# merkur-connect-pi-expansionboard.net
KiCad netlist of a schematic drawn in EAGLE
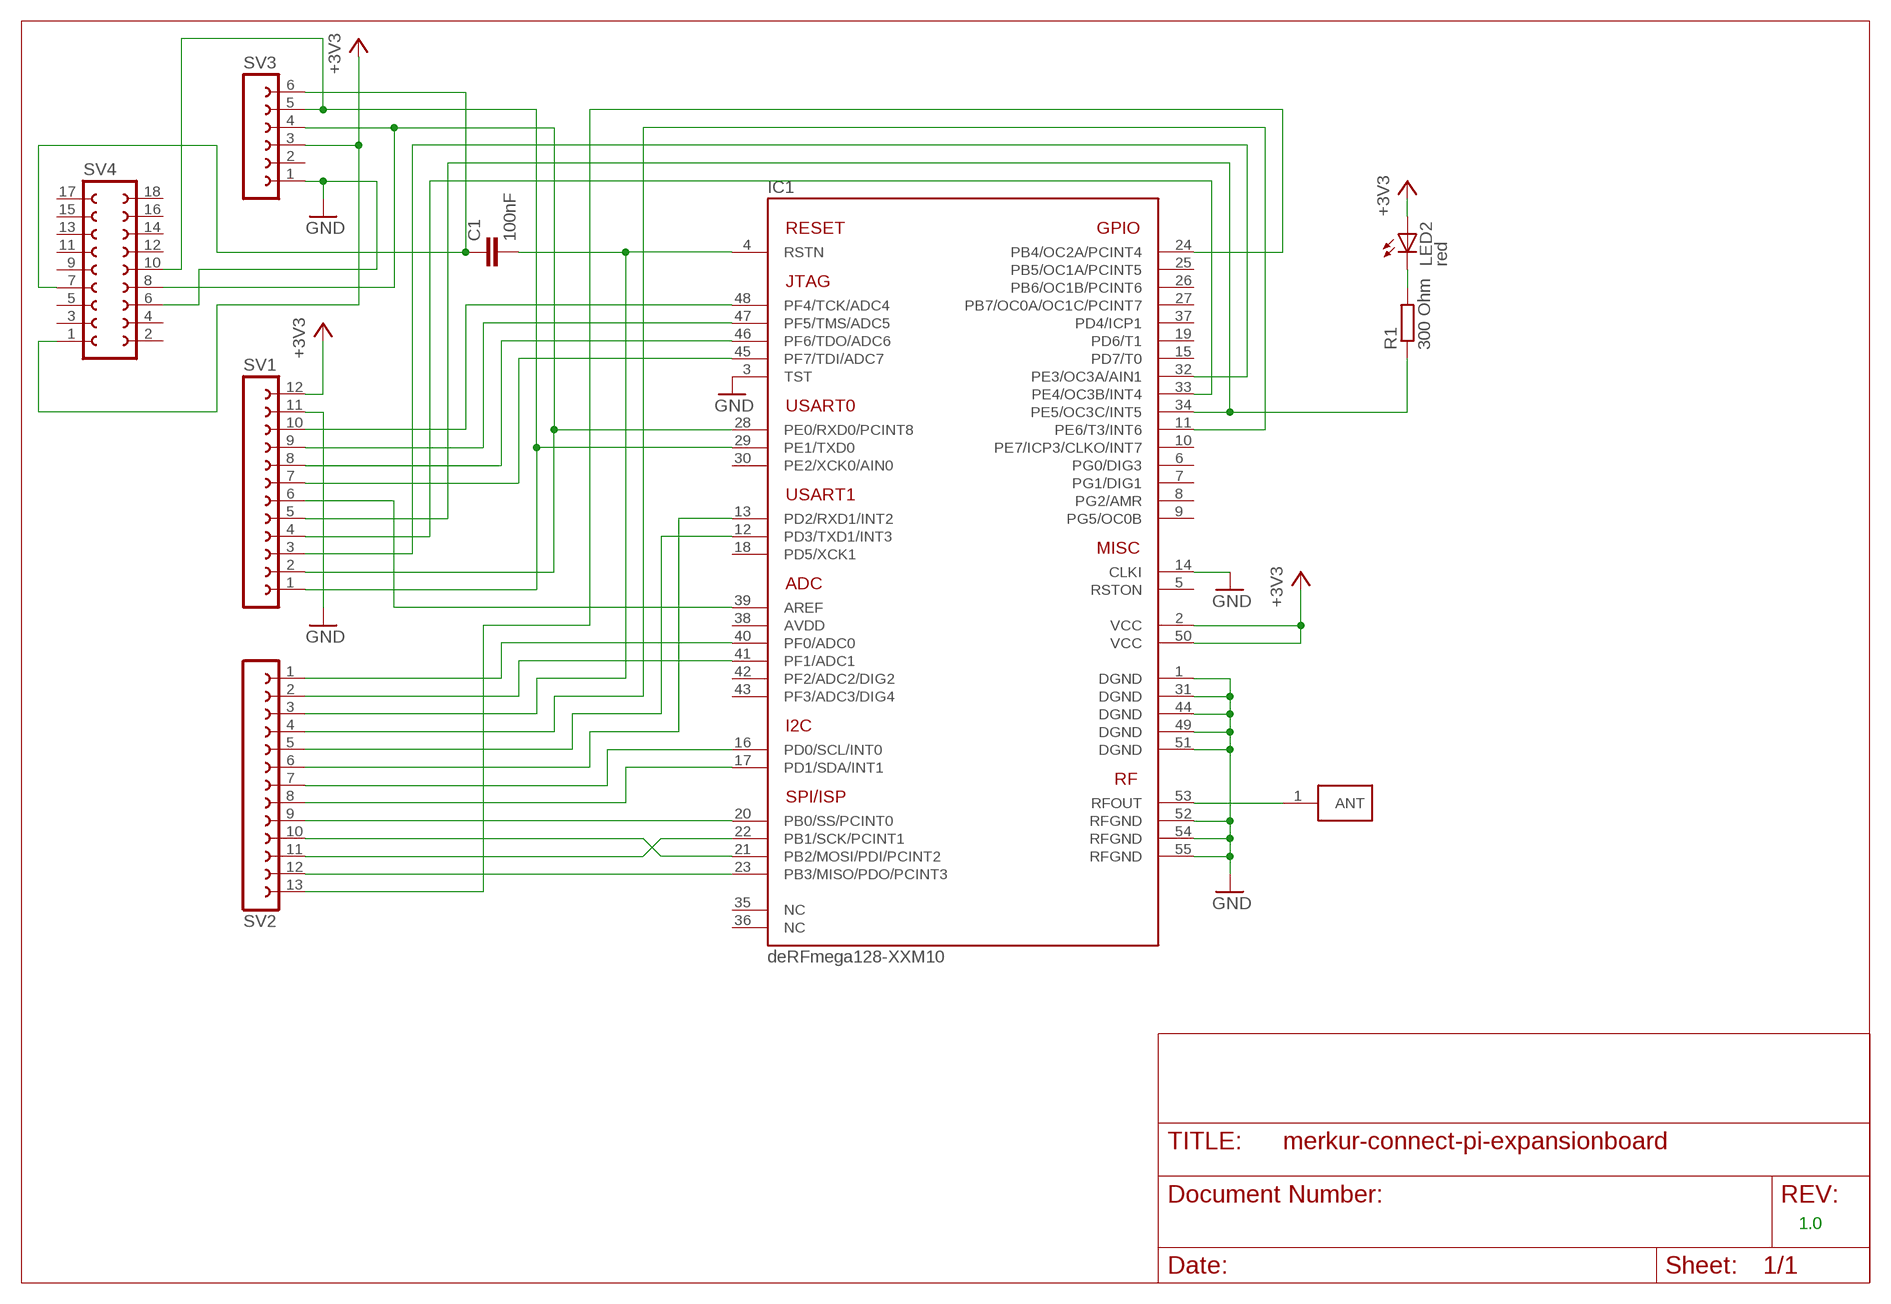
[diagram p0: schematic, sheet 1]

(export (version "E")
  (design (tool "Eeschema 10.0.6"))
  (components
    (comp (ref "C1")
      (value "100nF")
      (footprint "eagle-import:C0603")
      (libsource (lib "eagle-import") (part "C-EUC0603"))
    )
    (comp (ref "IC1")
      (value "DERFMEGA128-XXM10")
      (footprint "eagle-import:A-M10")
      (libsource (lib "eagle-import") (part "DERFMEGA128-XXM10"))
    )
    (comp (ref "LED2")
      (value "red")
      (footprint "eagle-import:CHIP-LED0603")
      (libsource (lib "eagle-import") (part "LEDCHIP-LED0603"))
    )
    (comp (ref "R1")
      (value "300 Ohm")
      (footprint "eagle-import:R0603")
      (libsource (lib "eagle-import") (part "R-EU_R0603"))
    )
    (comp (ref "SV1")
      (value "FE12-1")
      (footprint "eagle-import:FE12")
      (libsource (lib "eagle-import") (part "FE12-1"))
    )
    (comp (ref "SV2")
      (value "FE13-1")
      (footprint "eagle-import:FE13")
      (libsource (lib "eagle-import") (part "FE13-1"))
    )
    (comp (ref "SV3")
      (value "FE06-1")
      (footprint "eagle-import:FE06")
      (libsource (lib "eagle-import") (part "FE06-1"))
    )
    (comp (ref "SV4")
      (value "FE09-2")
      (footprint "eagle-import:FE09-2")
      (libsource (lib "eagle-import") (part "FE09-2"))
    )
    (comp (ref "U$1")
      (value "PAD")
      (footprint "eagle-import:FE05-1")
      (libsource (lib "eagle-import") (part "PAD"))
    )
  )
  (nets
    (net (code "1") (name "+3V3") (class "Default")
      (node (ref "IC1") (pin "2") (pinfunction "VCC_2") (pintype "power_in"))
      (node (ref "IC1") (pin "50") (pinfunction "VCC_50") (pintype "power_in"))
      (node (ref "LED2") (pin "A") (pinfunction "A_A") (pintype "passive"))
      (node (ref "SV1") (pin "12") (pinfunction "12_12") (pintype "passive"))
      (node (ref "SV3") (pin "3") (pinfunction "3_3") (pintype "passive"))
      (node (ref "SV4") (pin "1") (pinfunction "1_1") (pintype "passive"))
    )
    (net (code "2") (name "/AVDD") (class "Default")
      (node (ref "IC1") (pin "38") (pinfunction "AVDD_38") (pintype "power_in"))
    )
    (net (code "3") (name "GND") (class "Default")
      (node (ref "IC1") (pin "1") (pinfunction "DGND_1") (pintype "power_in"))
      (node (ref "IC1") (pin "14") (pinfunction "CLKI_14") (pintype "input"))
      (node (ref "IC1") (pin "3") (pinfunction "TST_3") (pintype "bidirectional"))
      (node (ref "IC1") (pin "31") (pinfunction "DGND_31") (pintype "power_in"))
      (node (ref "IC1") (pin "44") (pinfunction "DGND_44") (pintype "power_in"))
      (node (ref "IC1") (pin "49") (pinfunction "DGND_49") (pintype "power_in"))
      (node (ref "IC1") (pin "51") (pinfunction "DGND_51") (pintype "power_in"))
      (node (ref "IC1") (pin "52") (pinfunction "RFGND_52") (pintype "power_in"))
      (node (ref "IC1") (pin "54") (pinfunction "RFGND_54") (pintype "power_in"))
      (node (ref "IC1") (pin "55") (pinfunction "RFGND_55") (pintype "power_in"))
      (node (ref "SV1") (pin "11") (pinfunction "11_11") (pintype "passive"))
      (node (ref "SV3") (pin "1") (pinfunction "1_1") (pintype "passive"))
      (node (ref "SV4") (pin "6") (pinfunction "6_6") (pintype "passive"))
    )
    (net (code "4") (name "Net-(C1-Pad1)") (class "Default")
      (node (ref "C1") (pin "1") (pinfunction "1_1") (pintype "passive"))
      (node (ref "SV3") (pin "6") (pinfunction "6_6") (pintype "passive"))
      (node (ref "SV4") (pin "7") (pinfunction "7_7") (pintype "passive"))
    )
    (net (code "5") (name "Net-(IC1-AREF)") (class "Default")
      (node (ref "IC1") (pin "39") (pinfunction "AREF_39") (pintype "bidirectional"))
      (node (ref "SV1") (pin "6") (pinfunction "6_6") (pintype "passive"))
    )
    (net (code "6") (name "Net-(IC1-PB0{slash}SS{slash}PCINT0)") (class "Default")
      (node (ref "IC1") (pin "20") (pinfunction "PB0/SS/PCINT0_20") (pintype "bidirectional"))
      (node (ref "SV2") (pin "9") (pinfunction "9_9") (pintype "passive"))
    )
    (net (code "7") (name "Net-(IC1-PB1{slash}SCK{slash}PCINT1)") (class "Default")
      (node (ref "IC1") (pin "22") (pinfunction "PB1/SCK/PCINT1_22") (pintype "bidirectional"))
      (node (ref "SV2") (pin "11") (pinfunction "11_11") (pintype "passive"))
    )
    (net (code "8") (name "Net-(IC1-PB2{slash}MOSI{slash}PDI{slash}PCINT2)") (class "Default")
      (node (ref "IC1") (pin "21") (pinfunction "PB2/MOSI/PDI/PCINT2_21") (pintype "bidirectional"))
      (node (ref "SV2") (pin "10") (pinfunction "10_10") (pintype "passive"))
    )
    (net (code "9") (name "Net-(IC1-PB3{slash}MISO{slash}PDO{slash}PCINT3)") (class "Default")
      (node (ref "IC1") (pin "23") (pinfunction "PB3/MISO/PDO/PCINT3_23") (pintype "bidirectional"))
      (node (ref "SV2") (pin "12") (pinfunction "12_12") (pintype "passive"))
    )
    (net (code "10") (name "Net-(IC1-PB4{slash}OC2A{slash}PCINT4)") (class "Default")
      (node (ref "IC1") (pin "24") (pinfunction "PB4/OC2A/PCINT4_24") (pintype "bidirectional"))
      (node (ref "SV2") (pin "13") (pinfunction "13_13") (pintype "passive"))
    )
    (net (code "11") (name "Net-(IC1-PD0{slash}SCL{slash}INT0)") (class "Default")
      (node (ref "IC1") (pin "16") (pinfunction "PD0/SCL/INT0_16") (pintype "bidirectional"))
      (node (ref "SV2") (pin "7") (pinfunction "7_7") (pintype "passive"))
    )
    (net (code "12") (name "Net-(IC1-PD1{slash}SDA{slash}INT1)") (class "Default")
      (node (ref "IC1") (pin "17") (pinfunction "PD1/SDA/INT1_17") (pintype "bidirectional"))
      (node (ref "SV2") (pin "8") (pinfunction "8_8") (pintype "passive"))
    )
    (net (code "13") (name "Net-(IC1-PD2{slash}RXD1{slash}INT2)") (class "Default")
      (node (ref "IC1") (pin "13") (pinfunction "PD2/RXD1/INT2_13") (pintype "bidirectional"))
      (node (ref "SV2") (pin "6") (pinfunction "6_6") (pintype "passive"))
    )
    (net (code "14") (name "Net-(IC1-PD3{slash}TXD1{slash}INT3)") (class "Default")
      (node (ref "IC1") (pin "12") (pinfunction "PD3/TXD1/INT3_12") (pintype "bidirectional"))
      (node (ref "SV2") (pin "5") (pinfunction "5_5") (pintype "passive"))
    )
    (net (code "15") (name "Net-(IC1-PE0{slash}RXD0{slash}PCINT8)") (class "Default")
      (node (ref "IC1") (pin "28") (pinfunction "PE0/RXD0/PCINT8_28") (pintype "bidirectional"))
      (node (ref "SV1") (pin "2") (pinfunction "2_2") (pintype "passive"))
      (node (ref "SV3") (pin "4") (pinfunction "4_4") (pintype "passive"))
      (node (ref "SV4") (pin "8") (pinfunction "8_8") (pintype "passive"))
    )
    (net (code "16") (name "Net-(IC1-PE1{slash}TXD0)") (class "Default")
      (node (ref "IC1") (pin "29") (pinfunction "PE1/TXD0_29") (pintype "bidirectional"))
      (node (ref "SV1") (pin "1") (pinfunction "1_1") (pintype "passive"))
      (node (ref "SV3") (pin "5") (pinfunction "5_5") (pintype "passive"))
      (node (ref "SV4") (pin "10") (pinfunction "10_10") (pintype "passive"))
    )
    (net (code "17") (name "Net-(IC1-PE3{slash}OC3A{slash}AIN1)") (class "Default")
      (node (ref "IC1") (pin "32") (pinfunction "PE3/OC3A/AIN1_32") (pintype "bidirectional"))
      (node (ref "SV1") (pin "3") (pinfunction "3_3") (pintype "passive"))
    )
    (net (code "18") (name "Net-(IC1-PE4{slash}OC3B{slash}INT4)") (class "Default")
      (node (ref "IC1") (pin "33") (pinfunction "PE4/OC3B/INT4_33") (pintype "bidirectional"))
      (node (ref "SV1") (pin "4") (pinfunction "4_4") (pintype "passive"))
    )
    (net (code "19") (name "Net-(IC1-PE5{slash}OC3C{slash}INT5)") (class "Default")
      (node (ref "IC1") (pin "34") (pinfunction "PE5/OC3C/INT5_34") (pintype "bidirectional"))
      (node (ref "R1") (pin "1") (pinfunction "1_1") (pintype "passive"))
      (node (ref "SV1") (pin "5") (pinfunction "5_5") (pintype "passive"))
    )
    (net (code "20") (name "Net-(IC1-PE6{slash}T3{slash}INT6)") (class "Default")
      (node (ref "IC1") (pin "11") (pinfunction "PE6/T3/INT6_11") (pintype "bidirectional"))
      (node (ref "SV2") (pin "4") (pinfunction "4_4") (pintype "passive"))
    )
    (net (code "21") (name "Net-(IC1-PF0{slash}ADC0)") (class "Default")
      (node (ref "IC1") (pin "40") (pinfunction "PF0/ADC0_40") (pintype "bidirectional"))
      (node (ref "SV2") (pin "1") (pinfunction "1_1") (pintype "passive"))
    )
    (net (code "22") (name "Net-(IC1-PF1{slash}ADC1)") (class "Default")
      (node (ref "IC1") (pin "41") (pinfunction "PF1/ADC1_41") (pintype "bidirectional"))
      (node (ref "SV2") (pin "2") (pinfunction "2_2") (pintype "passive"))
    )
    (net (code "23") (name "Net-(IC1-PF4{slash}TCK{slash}ADC4)") (class "Default")
      (node (ref "IC1") (pin "48") (pinfunction "PF4/TCK/ADC4_48") (pintype "bidirectional"))
      (node (ref "SV1") (pin "10") (pinfunction "10_10") (pintype "passive"))
    )
    (net (code "24") (name "Net-(IC1-PF5{slash}TMS{slash}ADC5)") (class "Default")
      (node (ref "IC1") (pin "47") (pinfunction "PF5/TMS/ADC5_47") (pintype "bidirectional"))
      (node (ref "SV1") (pin "9") (pinfunction "9_9") (pintype "passive"))
    )
    (net (code "25") (name "Net-(IC1-PF6{slash}TDO{slash}ADC6)") (class "Default")
      (node (ref "IC1") (pin "46") (pinfunction "PF6/TDO/ADC6_46") (pintype "bidirectional"))
      (node (ref "SV1") (pin "8") (pinfunction "8_8") (pintype "passive"))
    )
    (net (code "26") (name "Net-(IC1-PF7{slash}TDI{slash}ADC7)") (class "Default")
      (node (ref "IC1") (pin "45") (pinfunction "PF7/TDI/ADC7_45") (pintype "bidirectional"))
      (node (ref "SV1") (pin "7") (pinfunction "7_7") (pintype "passive"))
    )
    (net (code "27") (name "Net-(IC1-RFOUT)") (class "Default")
      (node (ref "IC1") (pin "53") (pinfunction "RFOUT_53") (pintype "power_in"))
      (node (ref "U$1") (pin "1") (pinfunction "ANT_1") (pintype "output"))
    )
    (net (code "28") (name "Net-(IC1-RSTN)") (class "Default")
      (node (ref "C1") (pin "2") (pinfunction "2_2") (pintype "passive"))
      (node (ref "IC1") (pin "4") (pinfunction "RSTN_4") (pintype "input"))
      (node (ref "SV2") (pin "3") (pinfunction "3_3") (pintype "passive"))
    )
    (net (code "29") (name "Net-(LED2-PadC)") (class "Default")
      (node (ref "LED2") (pin "C") (pinfunction "C_C") (pintype "passive"))
      (node (ref "R1") (pin "2") (pinfunction "2_2") (pintype "passive"))
    )
    (net (code "30") (name "unconnected-(IC1-NC-Pad35)") (class "Default")
      (node (ref "IC1") (pin "35") (pinfunction "NC_35") (pintype "no_connect"))
    )
    (net (code "31") (name "unconnected-(IC1-NC-Pad36)") (class "Default")
      (node (ref "IC1") (pin "36") (pinfunction "NC_36") (pintype "no_connect"))
    )
    (net (code "32") (name "unconnected-(IC1-PB5{slash}OC1A{slash}PCINT5-Pad25)") (class "Default")
      (node (ref "IC1") (pin "25") (pinfunction "PB5/OC1A/PCINT5_25") (pintype "bidirectional"))
    )
    (net (code "33") (name "unconnected-(IC1-PB6{slash}OC1B{slash}PCINT6-Pad26)") (class "Default")
      (node (ref "IC1") (pin "26") (pinfunction "PB6/OC1B/PCINT6_26") (pintype "bidirectional"))
    )
    (net (code "34") (name "unconnected-(IC1-PB7{slash}OC0A{slash}OC1C{slash}PCINT7-Pad27)") (class "Default")
      (node (ref "IC1") (pin "27") (pinfunction "PB7/OC0A/OC1C/PCINT7_27") (pintype "bidirectional"))
    )
    (net (code "35") (name "unconnected-(IC1-PD4{slash}ICP1-Pad37)") (class "Default")
      (node (ref "IC1") (pin "37") (pinfunction "PD4/ICP1_37") (pintype "bidirectional"))
    )
    (net (code "36") (name "unconnected-(IC1-PD5{slash}XCK1-Pad18)") (class "Default")
      (node (ref "IC1") (pin "18") (pinfunction "PD5/XCK1_18") (pintype "bidirectional"))
    )
    (net (code "37") (name "unconnected-(IC1-PD6{slash}T1-Pad19)") (class "Default")
      (node (ref "IC1") (pin "19") (pinfunction "PD6/T1_19") (pintype "bidirectional"))
    )
    (net (code "38") (name "unconnected-(IC1-PD7{slash}T0-Pad15)") (class "Default")
      (node (ref "IC1") (pin "15") (pinfunction "PD7/T0_15") (pintype "bidirectional"))
    )
    (net (code "39") (name "unconnected-(IC1-PE2{slash}XCK0{slash}AIN0-Pad30)") (class "Default")
      (node (ref "IC1") (pin "30") (pinfunction "PE2/XCK0/AIN0_30") (pintype "bidirectional"))
    )
    (net (code "40") (name "unconnected-(IC1-PE7{slash}ICP3{slash}CLKO{slash}INT7-Pad10)") (class "Default")
      (node (ref "IC1") (pin "10") (pinfunction "PE7/ICP3/CLKO/INT7_10") (pintype "bidirectional"))
    )
    (net (code "41") (name "unconnected-(IC1-PF2{slash}ADC2{slash}DIG2-Pad42)") (class "Default")
      (node (ref "IC1") (pin "42") (pinfunction "PF2/ADC2/DIG2_42") (pintype "bidirectional"))
    )
    (net (code "42") (name "unconnected-(IC1-PF3{slash}ADC3{slash}DIG4-Pad43)") (class "Default")
      (node (ref "IC1") (pin "43") (pinfunction "PF3/ADC3/DIG4_43") (pintype "bidirectional"))
    )
    (net (code "43") (name "unconnected-(IC1-PG0{slash}DIG3-Pad6)") (class "Default")
      (node (ref "IC1") (pin "6") (pinfunction "PG0/DIG3_6") (pintype "bidirectional"))
    )
    (net (code "44") (name "unconnected-(IC1-PG1{slash}DIG1-Pad7)") (class "Default")
      (node (ref "IC1") (pin "7") (pinfunction "PG1/DIG1_7") (pintype "bidirectional"))
    )
    (net (code "45") (name "unconnected-(IC1-PG2{slash}AMR-Pad8)") (class "Default")
      (node (ref "IC1") (pin "8") (pinfunction "PG2/AMR_8") (pintype "bidirectional"))
    )
    (net (code "46") (name "unconnected-(IC1-PG5{slash}OC0B-Pad9)") (class "Default")
      (node (ref "IC1") (pin "9") (pinfunction "PG5/OC0B_9") (pintype "bidirectional"))
    )
    (net (code "47") (name "unconnected-(IC1-RSTON-Pad5)") (class "Default")
      (node (ref "IC1") (pin "5") (pinfunction "RSTON_5") (pintype "output"))
    )
    (net (code "48") (name "unconnected-(SV3-Pad2)") (class "Default")
      (node (ref "SV3") (pin "2") (pinfunction "2_2") (pintype "passive"))
    )
    (net (code "49") (name "unconnected-(SV4-Pad2)") (class "Default")
      (node (ref "SV4") (pin "2") (pinfunction "2_2") (pintype "passive"))
    )
    (net (code "50") (name "unconnected-(SV4-Pad3)") (class "Default")
      (node (ref "SV4") (pin "3") (pinfunction "3_3") (pintype "passive"))
    )
    (net (code "51") (name "unconnected-(SV4-Pad4)") (class "Default")
      (node (ref "SV4") (pin "4") (pinfunction "4_4") (pintype "passive"))
    )
    (net (code "52") (name "unconnected-(SV4-Pad5)") (class "Default")
      (node (ref "SV4") (pin "5") (pinfunction "5_5") (pintype "passive"))
    )
    (net (code "53") (name "unconnected-(SV4-Pad9)") (class "Default")
      (node (ref "SV4") (pin "9") (pinfunction "9_9") (pintype "passive"))
    )
    (net (code "54") (name "unconnected-(SV4-Pad11)") (class "Default")
      (node (ref "SV4") (pin "11") (pinfunction "11_11") (pintype "passive"))
    )
    (net (code "55") (name "unconnected-(SV4-Pad12)") (class "Default")
      (node (ref "SV4") (pin "12") (pinfunction "12_12") (pintype "passive"))
    )
    (net (code "56") (name "unconnected-(SV4-Pad13)") (class "Default")
      (node (ref "SV4") (pin "13") (pinfunction "13_13") (pintype "passive"))
    )
    (net (code "57") (name "unconnected-(SV4-Pad14)") (class "Default")
      (node (ref "SV4") (pin "14") (pinfunction "14_14") (pintype "passive"))
    )
    (net (code "58") (name "unconnected-(SV4-Pad15)") (class "Default")
      (node (ref "SV4") (pin "15") (pinfunction "15_15") (pintype "passive"))
    )
    (net (code "59") (name "unconnected-(SV4-Pad16)") (class "Default")
      (node (ref "SV4") (pin "16") (pinfunction "16_16") (pintype "passive"))
    )
    (net (code "60") (name "unconnected-(SV4-Pad17)") (class "Default")
      (node (ref "SV4") (pin "17") (pinfunction "17_17") (pintype "passive"))
    )
    (net (code "61") (name "unconnected-(SV4-Pad18)") (class "Default")
      (node (ref "SV4") (pin "18") (pinfunction "18_18") (pintype "passive"))
    )
  )
)
